# MainBoard_V100_CON.net
KiCad netlist of a schematic drawn in Altium Designer
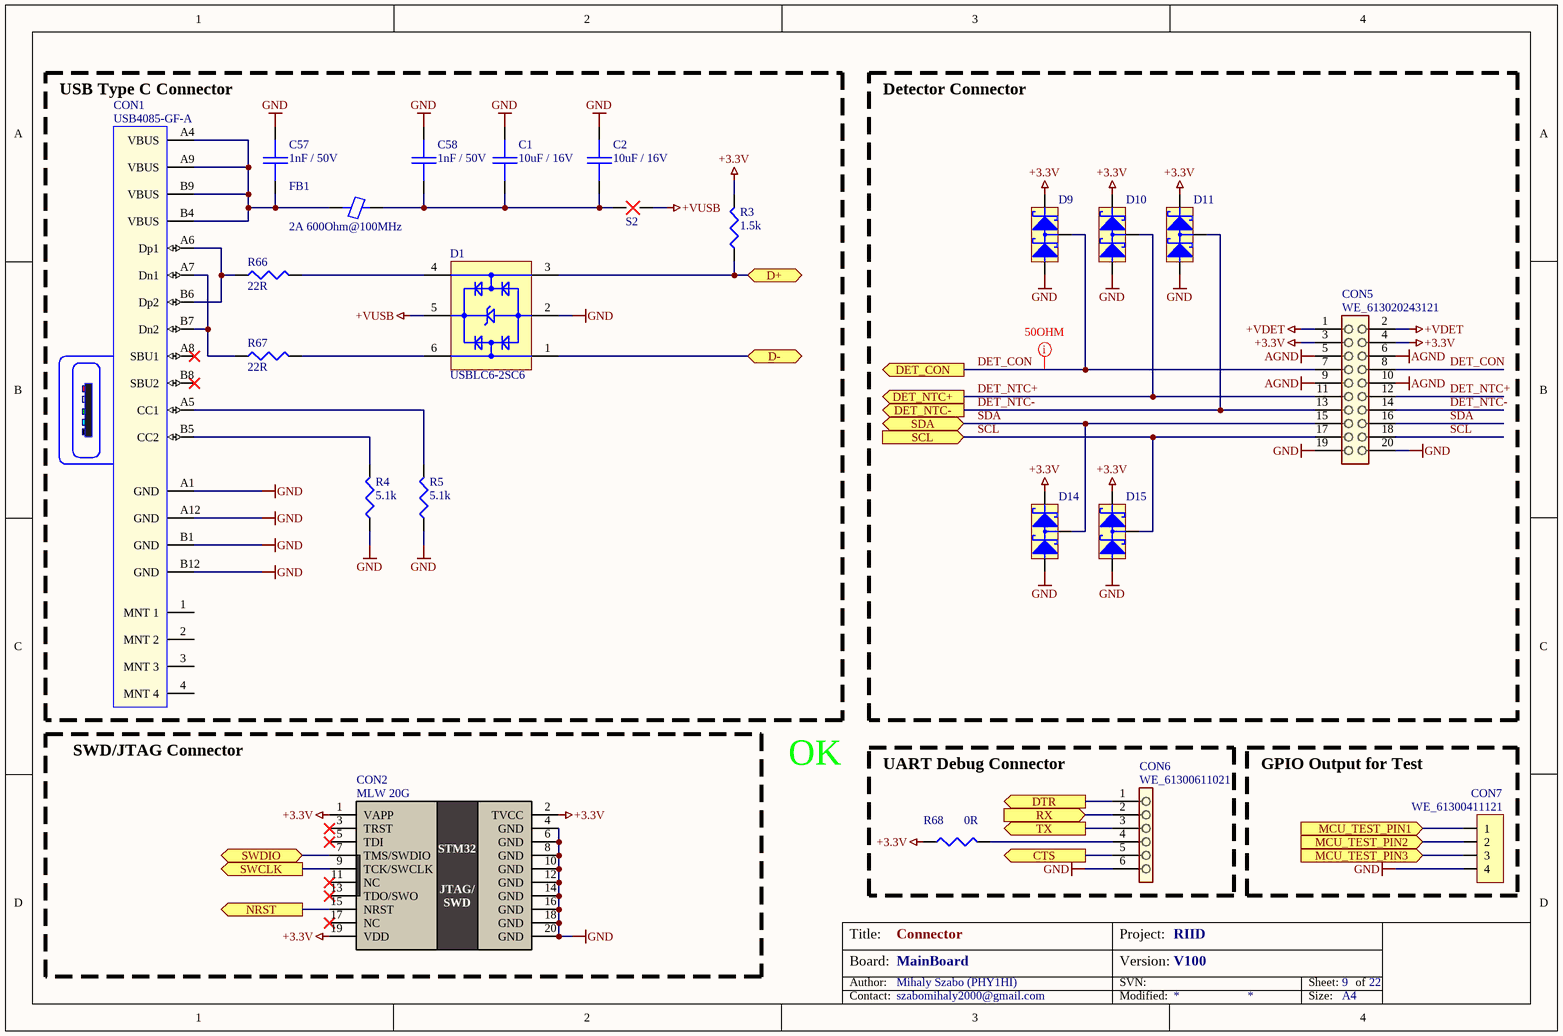
[diagram p0: MainBoard_V100_CON.SchDoc]

(export (version "E")
  (design (tool "Eeschema 10.0.6"))
  (components
    (comp (ref "C1")
      (value "10uF / 16V")
      (footprint "0805_C")
      (description "10uF 16V X5R")
      (fields (field (name "PART NUMBER") "SMD0805-10uF-16V"))
      (libsource (lib "ALTIUM_DB_LIB") (part "CAP_NONPOL"))
    )
    (comp (ref "C2")
      (value "10uF / 16V")
      (footprint "0805_C")
      (description "10uF 16V X5R")
      (fields (field (name "PART NUMBER") "SMD0805-10uF-16V"))
      (libsource (lib "ALTIUM_DB_LIB") (part "CAP_NONPOL"))
    )
    (comp (ref "C57")
      (value "1nF / 50V")
      (footprint "0805_C")
      (description "1nF 50V X7R")
      (fields (field (name "PART NUMBER") "SMD0805-1nF-50V"))
      (libsource (lib "ALTIUM_DB_LIB") (part "CAP_NONPOL"))
    )
    (comp (ref "C58")
      (value "1nF / 50V")
      (footprint "0805_C")
      (description "1nF 50V X7R")
      (fields (field (name "PART NUMBER") "SMD0805-1nF-50V"))
      (libsource (lib "ALTIUM_DB_LIB") (part "CAP_NONPOL"))
    )
    (comp (ref "CON1")
      (value "USB4085-GF-A")
      (footprint "FP-USB4085-GF-A-MFG")
      (description "USB Type C,USB 2.0, Rec,THT,  5A, 48V")
      (libsource (lib "ALTIUM_DB_LIB") (part "CON_USB2.0_TYPEC_THT"))
    )
    (comp (ref "CON2")
      (value "MLW 20G")
      (footprint "CON_MLW20G_TH")
      (description "JTAG/SWD Connector for ST-LINK/V2, 20pole")
      (fields (field (name "PART NUMBER") "JTAG/SWD ST-LINK/V2 20pole"))
      (libsource (lib "ALTIUM_DB_LIB") (part "JTAG/SWD_ST-LINK/V2_20P"))
    )
    (comp (ref "CON5")
      (value "WE_613020243121")
      (footprint "CON_HEADER20_2ROW_2.54_90DEG")
      (description "Board-To-Board Connector, 90DEG, 2.54 mm, 2x10 Contacts, Header, WR-PHD Series, Through Hole")
      (fields (field (name "PART NUMBER") "613020243121"))
      (libsource (lib "ALTIUM_DB_LIB") (part "CON20 (2 x 10)"))
    )
    (comp (ref "CON6")
      (value "WE_61300611021")
      (footprint "WE_61300611021")
      (description "Board-To-Board Connector, 90 DEG, 2.54 mm, 6 Contacts, Header, WR-PHD Series, Through Hole")
      (fields (field (name "PART NUMBER") "61300611021"))
      (libsource (lib "ALTIUM_DB_LIB") (part "CON6 (1 x 6)"))
    )
    (comp (ref "CON7")
      (value "WE_61300411121")
      (footprint "CON4_SIMPLE_TH")
      (description "Board-To-Board Connector, Vertical, 2.54 mm, 4 Contacts, Header, WR-PHD Series, Through Hole")
      (fields (field (name "PART NUMBER") "Pin Header 04 Pole 1 Row 2.54mm"))
      (libsource (lib "ALTIUM_DB_LIB") (part "CON4 (1 x 4)"))
    )
    (comp (ref "D1")
      (value "USBLC6-2SC6")
      (footprint "SOT-23-6L")
      (description "Very low capacitance ESD protection, 3.5 pF, -40 to 125 degC, 6-Pin SOT23")
      (fields (field (name "MANUFACTURER") "STMicroelectronics"))
      (libsource (lib "ALTIUM_DB_LIB") (part "USBLC6-2SC6"))
    )
    (comp (ref "D9")
      (value "BAS70-04")
      (footprint "SOT-23")
      (description "Small Signal Schottky Diode, Dual Series, 70 V, 15 mA, 1 V, 100 mA, 150 °C")
      (fields (field (name "PART NUMBER") "BAS70-04LT1G"))
      (libsource (lib "ALTIUM_DB_LIB") (part "BAS70-04"))
    )
    (comp (ref "D10")
      (value "BAS70-04")
      (footprint "SOT-23")
      (description "Small Signal Schottky Diode, Dual Series, 70 V, 15 mA, 1 V, 100 mA, 150 °C")
      (fields (field (name "PART NUMBER") "BAS70-04LT1G"))
      (libsource (lib "ALTIUM_DB_LIB") (part "BAS70-04"))
    )
    (comp (ref "D11")
      (value "BAS70-04")
      (footprint "SOT-23")
      (description "Small Signal Schottky Diode, Dual Series, 70 V, 15 mA, 1 V, 100 mA, 150 °C")
      (fields (field (name "PART NUMBER") "BAS70-04LT1G"))
      (libsource (lib "ALTIUM_DB_LIB") (part "BAS70-04"))
    )
    (comp (ref "D14")
      (value "BAS70-04")
      (footprint "SOT-23")
      (description "Small Signal Schottky Diode, Dual Series, 70 V, 15 mA, 1 V, 100 mA, 150 °C")
      (fields (field (name "PART NUMBER") "BAS70-04LT1G"))
      (libsource (lib "ALTIUM_DB_LIB") (part "BAS70-04"))
    )
    (comp (ref "D15")
      (value "BAS70-04")
      (footprint "SOT-23")
      (description "Small Signal Schottky Diode, Dual Series, 70 V, 15 mA, 1 V, 100 mA, 150 °C")
      (fields (field (name "PART NUMBER") "BAS70-04LT1G"))
      (libsource (lib "ALTIUM_DB_LIB") (part "BAS70-04"))
    )
    (comp (ref "FB1")
      (value "2A 600Ohm@100MHz")
      (footprint "0805_FB")
      (description "Ferrite bead 2A 600Ohm@100MHz")
      (fields (field (name "PART NUMBER") "LCBB-601 SMD"))
      (libsource (lib "ALTIUM_DB_LIB") (part "FERRITE_BEAD"))
    )
    (comp (ref "R3")
      (value "1.5k")
      (footprint "0805")
      (description "1.5k 0805 0.125W 1%")
      (fields (field (name "PART NUMBER") "SMD0805-1.5k-1%"))
      (libsource (lib "ALTIUM_DB_LIB") (part "RESISTOR"))
    )
    (comp (ref "R4")
      (value "5.1k")
      (footprint "0805")
      (description "5.1k 0805 0.125W 5%")
      (fields (field (name "PART NUMBER") "SMD0805-5.1k 5%"))
      (libsource (lib "ALTIUM_DB_LIB") (part "RESISTOR"))
    )
    (comp (ref "R5")
      (value "5.1k")
      (footprint "0805")
      (description "5.1k 0805 0.125W 5%")
      (fields (field (name "PART NUMBER") "SMD0805-5.1k 5%"))
      (libsource (lib "ALTIUM_DB_LIB") (part "RESISTOR"))
    )
    (comp (ref "R66")
      (value "22R")
      (footprint "0603")
      (description "22R 0603 0.1W 5%")
      (fields (field (name "PART NUMBER") "SMD0603-22R-5%"))
      (libsource (lib "ALTIUM_DB_LIB") (part "RESISTOR"))
    )
    (comp (ref "R67")
      (value "22R")
      (footprint "0603")
      (description "22R 0603 0.1W 5%")
      (fields (field (name "PART NUMBER") "SMD0603-22R-5%"))
      (libsource (lib "ALTIUM_DB_LIB") (part "RESISTOR"))
    )
    (comp (ref "R68")
      (value "0R")
      (footprint "0805")
      (description "0R 0805 0.125W 5%")
      (fields (field (name "PART NUMBER") "0 R 5%"))
      (libsource (lib "ALTIUM_DB_LIB") (part "RESISTOR"))
    )
    (comp (ref "S2")
      (value "SPLITER")
      (footprint "SPLITER2_30mil_9mil")
      (description "SPLITER2_30mil_9mil")
      (libsource (lib "ALTIUM_DB_LIB") (part "SPLITER"))
    )
  )
  (nets
    (net (code "1") (name "+3.3V") (class "Default")
      (node (ref "CON2") (pin "1") (pinfunction "VAPP_1") (pintype "passive"))
      (node (ref "CON2") (pin "19") (pinfunction "VDD_19") (pintype "passive"))
      (node (ref "CON2") (pin "2") (pinfunction "TVCC_2") (pintype "passive"))
      (node (ref "CON5") (pin "3") (pinfunction "3_3") (pintype "passive"))
      (node (ref "CON5") (pin "4") (pinfunction "4_4") (pintype "passive"))
      (node (ref "D10") (pin "2") (pinfunction "2_2") (pintype "passive"))
      (node (ref "D11") (pin "2") (pinfunction "2_2") (pintype "passive"))
      (node (ref "D14") (pin "2") (pinfunction "2_2") (pintype "passive"))
      (node (ref "D15") (pin "2") (pinfunction "2_2") (pintype "passive"))
      (node (ref "D9") (pin "2") (pinfunction "2_2") (pintype "passive"))
      (node (ref "R3") (pin "2") (pintype "passive"))
      (node (ref "R68") (pin "1") (pintype "passive"))
    )
    (net (code "2") (name "+VDET") (class "Default")
      (node (ref "CON5") (pin "1") (pinfunction "1_1") (pintype "passive"))
      (node (ref "CON5") (pin "2") (pinfunction "2_2") (pintype "passive"))
    )
    (net (code "3") (name "+VUSB") (class "Default")
      (node (ref "D1") (pin "5") (pinfunction "VBUS_5") (pintype "passive"))
      (node (ref "S2") (pin "2") (pinfunction "2_2") (pintype "passive"))
    )
    (net (code "4") (name "/CTS") (class "Default")
      (node (ref "CON6") (pin "5") (pinfunction "5_5") (pintype "passive"))
    )
    (net (code "5") (name "/D+") (class "Default")
      (node (ref "D1") (pin "3") (pinfunction "I/O_2_3") (pintype "passive"))
      (node (ref "R3") (pin "1") (pintype "passive"))
    )
    (net (code "6") (name "/D-") (class "Default")
      (node (ref "D1") (pin "1") (pinfunction "I/O_1_1") (pintype "passive"))
    )
    (net (code "7") (name "/DET_CON") (class "Default")
      (node (ref "CON5") (pin "7") (pinfunction "7_7") (pintype "passive"))
      (node (ref "CON5") (pin "8") (pinfunction "8_8") (pintype "passive"))
      (node (ref "D9") (pin "3") (pinfunction "3_3") (pintype "passive"))
    )
    (net (code "8") (name "/DET_NTC+") (class "Default")
      (node (ref "CON5") (pin "11") (pinfunction "11_11") (pintype "passive"))
      (node (ref "CON5") (pin "12") (pinfunction "12_12") (pintype "passive"))
      (node (ref "D10") (pin "3") (pinfunction "3_3") (pintype "passive"))
    )
    (net (code "9") (name "/DET_NTC-") (class "Default")
      (node (ref "CON5") (pin "13") (pinfunction "13_13") (pintype "passive"))
      (node (ref "CON5") (pin "14") (pinfunction "14_14") (pintype "passive"))
      (node (ref "D11") (pin "3") (pinfunction "3_3") (pintype "passive"))
    )
    (net (code "10") (name "/DTR") (class "Default")
      (node (ref "CON6") (pin "1") (pinfunction "1_1") (pintype "passive"))
    )
    (net (code "11") (name "/MCU_TEST_PIN1") (class "Default")
      (node (ref "CON7") (pin "1") (pinfunction "1_1") (pintype "passive"))
    )
    (net (code "12") (name "/MCU_TEST_PIN2") (class "Default")
      (node (ref "CON7") (pin "2") (pinfunction "2_2") (pintype "passive"))
    )
    (net (code "13") (name "/MCU_TEST_PIN3") (class "Default")
      (node (ref "CON7") (pin "3") (pinfunction "3_3") (pintype "passive"))
    )
    (net (code "14") (name "/NRST") (class "Default")
      (node (ref "CON2") (pin "15") (pinfunction "NRST_15") (pintype "passive"))
    )
    (net (code "15") (name "/RX") (class "Default")
      (node (ref "CON6") (pin "2") (pinfunction "2_2") (pintype "passive"))
    )
    (net (code "16") (name "/SCL") (class "Default")
      (node (ref "CON5") (pin "17") (pinfunction "17_17") (pintype "passive"))
      (node (ref "CON5") (pin "18") (pinfunction "18_18") (pintype "passive"))
      (node (ref "D15") (pin "3") (pinfunction "3_3") (pintype "passive"))
    )
    (net (code "17") (name "/SDA") (class "Default")
      (node (ref "CON5") (pin "15") (pinfunction "15_15") (pintype "passive"))
      (node (ref "CON5") (pin "16") (pinfunction "16_16") (pintype "passive"))
      (node (ref "D14") (pin "3") (pinfunction "3_3") (pintype "passive"))
    )
    (net (code "18") (name "/SWCLK") (class "Default")
      (node (ref "CON2") (pin "9") (pinfunction "TCK/SWCLK_9") (pintype "passive"))
    )
    (net (code "19") (name "/SWDIO") (class "Default")
      (node (ref "CON2") (pin "7") (pinfunction "TMS/SWDIO_7") (pintype "passive"))
    )
    (net (code "20") (name "/TX") (class "Default")
      (node (ref "CON6") (pin "3") (pinfunction "3_3") (pintype "passive"))
    )
    (net (code "21") (name "AGND") (class "Default")
      (node (ref "CON5") (pin "10") (pinfunction "10_10") (pintype "passive"))
      (node (ref "CON5") (pin "5") (pinfunction "5_5") (pintype "passive"))
      (node (ref "CON5") (pin "6") (pinfunction "6_6") (pintype "passive"))
      (node (ref "CON5") (pin "9") (pinfunction "9_9") (pintype "passive"))
    )
    (net (code "22") (name "GND") (class "Default")
      (node (ref "C1") (pin "1") (pintype "passive"))
      (node (ref "C2") (pin "1") (pintype "passive"))
      (node (ref "C57") (pin "2") (pintype "passive"))
      (node (ref "C58") (pin "2") (pintype "passive"))
      (node (ref "CON1") (pin "A1") (pinfunction "GND_A1") (pintype "power_in"))
      (node (ref "CON1") (pin "A12") (pinfunction "GND_A12") (pintype "power_in"))
      (node (ref "CON1") (pin "B1") (pinfunction "GND_B1") (pintype "power_in"))
      (node (ref "CON1") (pin "B12") (pinfunction "GND_B12") (pintype "power_in"))
      (node (ref "CON2") (pin "10") (pinfunction "GND_10") (pintype "passive"))
      (node (ref "CON2") (pin "12") (pinfunction "GND_12") (pintype "passive"))
      (node (ref "CON2") (pin "14") (pinfunction "GND_14") (pintype "passive"))
      (node (ref "CON2") (pin "16") (pinfunction "GND_16") (pintype "passive"))
      (node (ref "CON2") (pin "18") (pinfunction "GND_18") (pintype "passive"))
      (node (ref "CON2") (pin "20") (pinfunction "GND_20") (pintype "passive"))
      (node (ref "CON2") (pin "4") (pinfunction "GND_4") (pintype "passive"))
      (node (ref "CON2") (pin "6") (pinfunction "GND_6") (pintype "passive"))
      (node (ref "CON2") (pin "8") (pinfunction "GND_8") (pintype "passive"))
      (node (ref "CON5") (pin "19") (pinfunction "19_19") (pintype "passive"))
      (node (ref "CON5") (pin "20") (pinfunction "20_20") (pintype "passive"))
      (node (ref "CON6") (pin "6") (pinfunction "6_6") (pintype "passive"))
      (node (ref "CON7") (pin "4") (pinfunction "4_4") (pintype "passive"))
      (node (ref "D1") (pin "2") (pinfunction "GND_2") (pintype "passive"))
      (node (ref "D10") (pin "1") (pinfunction "1_1") (pintype "passive"))
      (node (ref "D11") (pin "1") (pinfunction "1_1") (pintype "passive"))
      (node (ref "D14") (pin "1") (pinfunction "1_1") (pintype "passive"))
      (node (ref "D15") (pin "1") (pinfunction "1_1") (pintype "passive"))
      (node (ref "D9") (pin "1") (pinfunction "1_1") (pintype "passive"))
      (node (ref "R4") (pin "1") (pintype "passive"))
      (node (ref "R5") (pin "1") (pintype "passive"))
    )
    (net (code "23") (name "Net-(C1-Pad2)") (class "Default")
      (node (ref "C1") (pin "2") (pintype "passive"))
      (node (ref "C2") (pin "2") (pintype "passive"))
      (node (ref "C58") (pin "1") (pintype "passive"))
      (node (ref "FB1") (pin "1") (pinfunction "1_1") (pintype "passive"))
      (node (ref "S2") (pin "1") (pinfunction "1_1") (pintype "passive"))
    )
    (net (code "24") (name "Net-(C57-Pad1)") (class "Default")
      (node (ref "C57") (pin "1") (pintype "passive"))
      (node (ref "CON1") (pin "A4") (pinfunction "VBUS_A4") (pintype "power_in"))
      (node (ref "CON1") (pin "A9") (pinfunction "VBUS_A9") (pintype "power_in"))
      (node (ref "CON1") (pin "B4") (pinfunction "VBUS_B4") (pintype "power_in"))
      (node (ref "CON1") (pin "B9") (pinfunction "VBUS_B9") (pintype "power_in"))
      (node (ref "FB1") (pin "2") (pinfunction "2_2") (pintype "passive"))
    )
    (net (code "25") (name "Net-(CON1-CC1)") (class "Default")
      (node (ref "CON1") (pin "A5") (pinfunction "CC1_A5") (pintype "bidirectional"))
      (node (ref "R5") (pin "2") (pintype "passive"))
    )
    (net (code "26") (name "Net-(CON1-CC2)") (class "Default")
      (node (ref "CON1") (pin "B5") (pinfunction "CC2_B5") (pintype "bidirectional"))
      (node (ref "R4") (pin "2") (pintype "passive"))
    )
    (net (code "27") (name "Net-(CON1-Dn1)") (class "Default")
      (node (ref "CON1") (pin "A7") (pinfunction "Dn1_A7") (pintype "bidirectional"))
      (node (ref "CON1") (pin "B7") (pinfunction "Dn2_B7") (pintype "bidirectional"))
      (node (ref "R67") (pin "1") (pintype "passive"))
    )
    (net (code "28") (name "Net-(CON1-Dp1)") (class "Default")
      (node (ref "CON1") (pin "A6") (pinfunction "Dp1_A6") (pintype "bidirectional"))
      (node (ref "CON1") (pin "B6") (pinfunction "Dp2_B6") (pintype "bidirectional"))
      (node (ref "R66") (pin "1") (pintype "passive"))
    )
    (net (code "29") (name "Net-(CON6-Pad4)") (class "Default")
      (node (ref "CON6") (pin "4") (pinfunction "4_4") (pintype "passive"))
      (node (ref "R68") (pin "2") (pintype "passive"))
    )
    (net (code "30") (name "Net-(D1-I{slash}O_3)") (class "Default")
      (node (ref "D1") (pin "4") (pinfunction "I/O_3_4") (pintype "passive"))
      (node (ref "R66") (pin "2") (pintype "passive"))
    )
    (net (code "31") (name "Net-(D1-I{slash}O_4)") (class "Default")
      (node (ref "D1") (pin "6") (pinfunction "I/O_4_6") (pintype "passive"))
      (node (ref "R67") (pin "2") (pintype "passive"))
    )
    (net (code "32") (name "unconnected-(CON1-MNT_1-Pad1)") (class "Default")
      (node (ref "CON1") (pin "1") (pinfunction "MNT_1_1") (pintype "passive"))
    )
    (net (code "33") (name "unconnected-(CON1-MNT_2-Pad2)") (class "Default")
      (node (ref "CON1") (pin "2") (pinfunction "MNT_2_2") (pintype "passive"))
    )
    (net (code "34") (name "unconnected-(CON1-MNT_3-Pad3)") (class "Default")
      (node (ref "CON1") (pin "3") (pinfunction "MNT_3_3") (pintype "passive"))
    )
    (net (code "35") (name "unconnected-(CON1-MNT_4-Pad4)") (class "Default")
      (node (ref "CON1") (pin "4") (pinfunction "MNT_4_4") (pintype "passive"))
    )
    (net (code "36") (name "unconnected-(CON1-SBU1-PadA8)") (class "Default")
      (node (ref "CON1") (pin "A8") (pinfunction "SBU1_A8") (pintype "bidirectional+no_connect"))
    )
    (net (code "37") (name "unconnected-(CON1-SBU2-PadB8)") (class "Default")
      (node (ref "CON1") (pin "B8") (pinfunction "SBU2_B8") (pintype "bidirectional+no_connect"))
    )
    (net (code "38") (name "unconnected-(CON2-NC-Pad11)") (class "Default")
      (node (ref "CON2") (pin "11") (pinfunction "NC_11") (pintype "passive+no_connect"))
    )
    (net (code "39") (name "unconnected-(CON2-NC-Pad17)") (class "Default")
      (node (ref "CON2") (pin "17") (pinfunction "NC_17") (pintype "passive+no_connect"))
    )
    (net (code "40") (name "unconnected-(CON2-TDI-Pad5)") (class "Default")
      (node (ref "CON2") (pin "5") (pinfunction "TDI_5") (pintype "passive+no_connect"))
    )
    (net (code "41") (name "unconnected-(CON2-TDO{slash}SWO-Pad13)") (class "Default")
      (node (ref "CON2") (pin "13") (pinfunction "TDO/SWO_13") (pintype "passive+no_connect"))
    )
    (net (code "42") (name "unconnected-(CON2-TRST-Pad3)") (class "Default")
      (node (ref "CON2") (pin "3") (pinfunction "TRST_3") (pintype "passive+no_connect"))
    )
  )
)
